# DAC_OutputStage_4.net
KiCad netlist of a schematic drawn in EAGLE
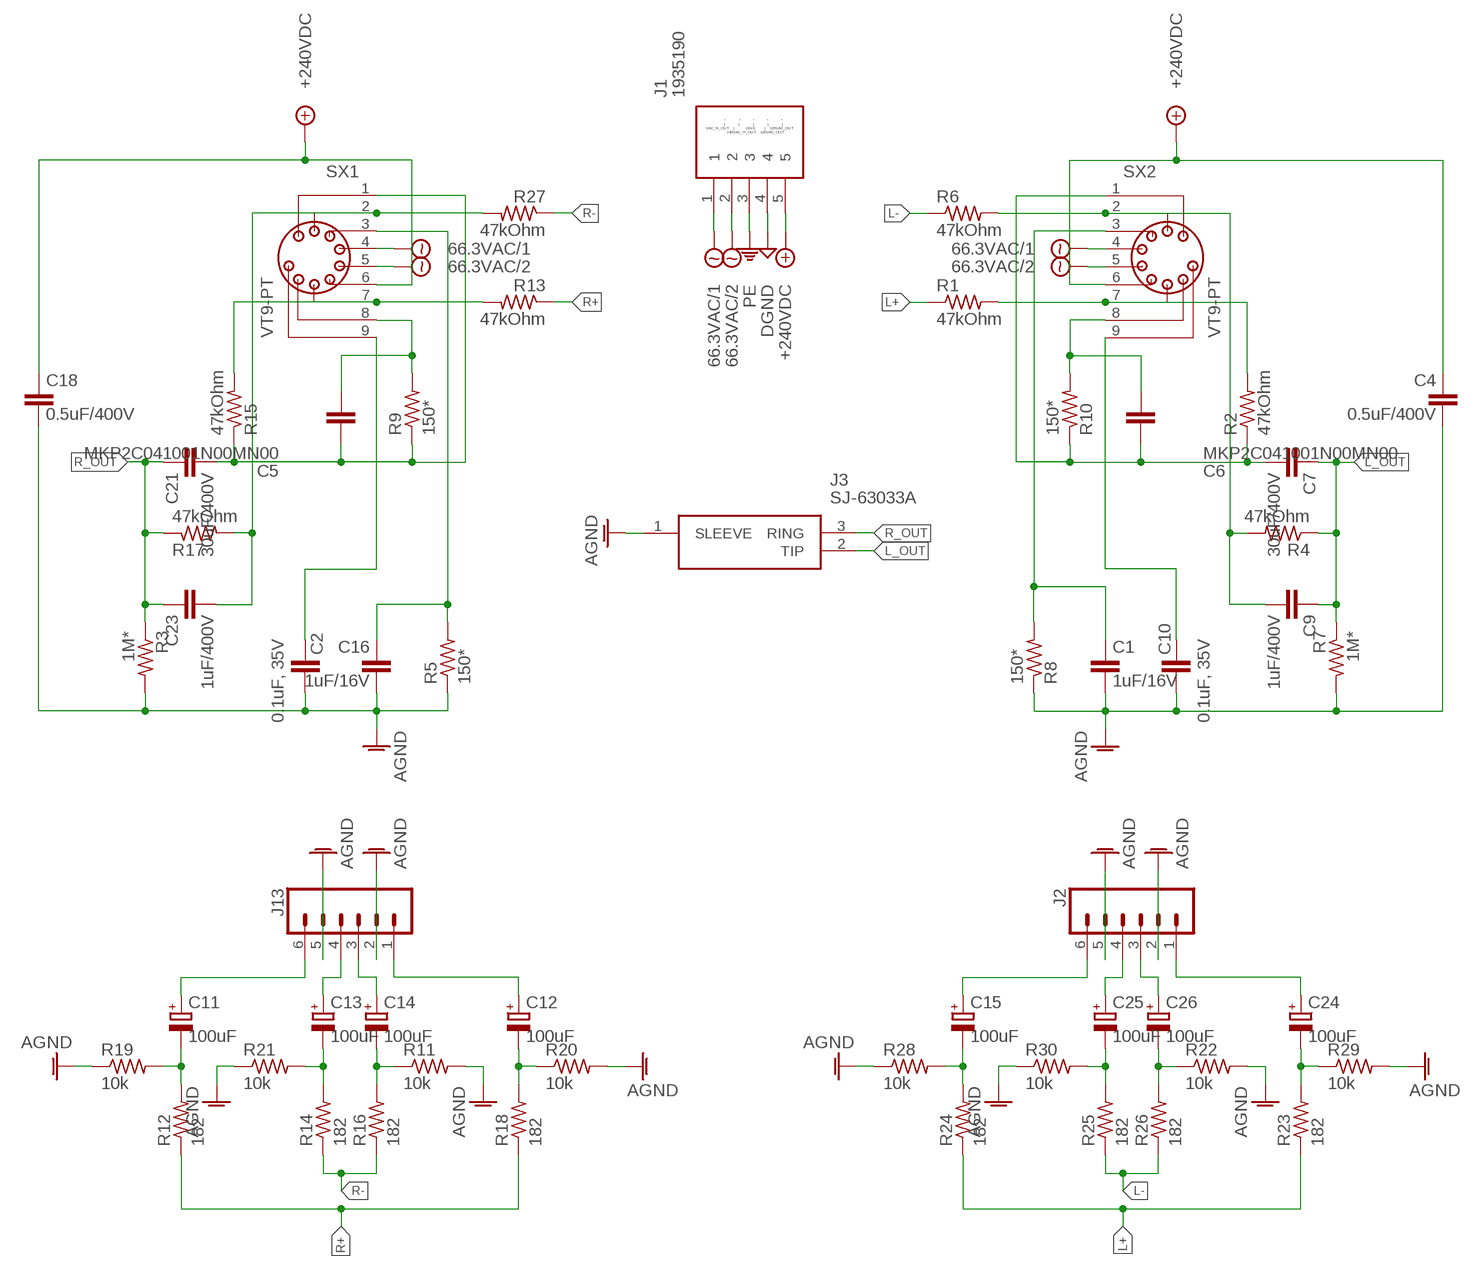
[diagram p0: schematic, sheet 1]

(export (version "E")
  (design (tool "Eeschema 10.0.6"))
  (components
    (comp (ref "C1")
      (value "1uF/16V")
      (footprint "eagle-import:MKP2C041001N00MN00")
      (fields
        (field (name "MANUFACTURER_PART_NUMBER") "MKP2C041001N00MN00")
        (field (name "MOUSER_PART_NUMBER") "505-MKP2C0411NMN")
      )
      (libsource (lib "eagle-import") (part "MKP2C041001N00MN00"))
    )
    (comp (ref "C2")
      (value "0.1uF, 35V")
      (footprint "eagle-import:MKS4B031002A00JC00")
      (fields
        (field (name "MANUFACTURER_PART_NUMBER") "MKS4B031002A00JC00")
        (field (name "MOUSER_PART_NUMBER") "505-MKS4B0312AJC")
      )
      (libsource (lib "eagle-import") (part "MKS4B031002A00JC00"))
    )
    (comp (ref "C4")
      (value "0.5uF/400V")
      (footprint "eagle-import:MKP4G034705D00KSSD")
      (fields
        (field (name "MANUFACTURER_PART_NUMBER") "MKP4G034705D00KSSD")
        (field (name "MOUSER_PART_NUMBER") "505-MKP4G034705DKSSD")
      )
      (libsource (lib "eagle-import") (part "MKP4G034705D00KSSD"))
    )
    (comp (ref "C5")
      (value "MKP2C041001N00MN00")
      (footprint "eagle-import:MKP2C041001N00MN00")
      (fields (field (name "MOUSER_PART_NUMBER") "505-MKP2C0411NMN"))
      (libsource (lib "eagle-import") (part "MKP2C041001N00MN00"))
    )
    (comp (ref "C6")
      (value "MKP2C041001N00MN00")
      (footprint "eagle-import:MKP2C041001N00MN00")
      (fields (field (name "MOUSER_PART_NUMBER") "505-MKP2C0411NMN"))
      (libsource (lib "eagle-import") (part "MKP2C041001N00MN00"))
    )
    (comp (ref "C7")
      (value "30uF/400V")
      (footprint "eagle-import:DCP4G053006ID2KSSD")
      (fields
        (field (name "MANUFACTURER_PART_NUMBER") "DCP4G053006ID2KSSD")
        (field (name "MOUSER_PART_NUMBER") "505-DCP4G0536ID2KSSD")
      )
      (libsource (lib "eagle-import") (part "DCP4G053006ID2KSSD"))
    )
    (comp (ref "C9")
      (value "1uF/400V")
      (footprint "eagle-import:MKP4G041005I00JSSD")
      (fields
        (field (name "MANUFACTURER_PART_NUMBER") "MKP4G041005I00JSSD")
        (field (name "MOUSER_PART_NUMBER") "505-MKP4G041005I00JS")
      )
      (libsource (lib "eagle-import") (part "MKP4G041005I00JSSD"))
    )
    (comp (ref "C10")
      (value "0.1uF, 35V")
      (footprint "eagle-import:MKS4B031002A00JC00")
      (fields
        (field (name "MANUFACTURER_PART_NUMBER") "MKS4B031002A00JC00")
        (field (name "MOUSER_PART_NUMBER") "505-MKS4B0312AJC")
      )
      (libsource (lib "eagle-import") (part "MKS4B031002A00JC00"))
    )
    (comp (ref "C11")
      (value "100uF")
      (footprint "eagle-import:CAPPRD350W60D825H1300")
      (fields
        (field (name "ARROW_PART_NUMBER") "UFW1H101MPD1TD")
        (field (name "MOUSER_PART_NUMBER") "647-UFW1H101MPD1TD")
      )
      (libsource (lib "eagle-import") (part "UFW1H101MPD1TD"))
    )
    (comp (ref "C12")
      (value "100uF")
      (footprint "eagle-import:CAPPRD350W60D825H1300")
      (fields
        (field (name "ARROW_PART_NUMBER") "UFW1H101MPD1TD")
        (field (name "MOUSER_PART_NUMBER") "647-UFW1H101MPD1TD")
      )
      (libsource (lib "eagle-import") (part "UFW1H101MPD1TD"))
    )
    (comp (ref "C13")
      (value "100uF")
      (footprint "eagle-import:CAPPRD350W60D825H1300")
      (fields
        (field (name "ARROW_PART_NUMBER") "UFW1H101MPD1TD")
        (field (name "MOUSER_PART_NUMBER") "647-UFW1H101MPD1TD")
      )
      (libsource (lib "eagle-import") (part "UFW1H101MPD1TD"))
    )
    (comp (ref "C14")
      (value "100uF")
      (footprint "eagle-import:CAPPRD350W60D825H1300")
      (fields
        (field (name "ARROW_PART_NUMBER") "UFW1H101MPD1TD")
        (field (name "MOUSER_PART_NUMBER") "647-UFW1H101MPD1TD")
      )
      (libsource (lib "eagle-import") (part "UFW1H101MPD1TD"))
    )
    (comp (ref "C15")
      (value "100uF")
      (footprint "eagle-import:CAPPRD350W60D825H1300")
      (fields
        (field (name "ARROW_PART_NUMBER") "UFW1H101MPD1TD")
        (field (name "MOUSER_PART_NUMBER") "647-UFW1H101MPD1TD")
      )
      (libsource (lib "eagle-import") (part "UFW1H101MPD1TD"))
    )
    (comp (ref "C16")
      (value "1uF/16V")
      (footprint "eagle-import:MKP2C041001N00MN00")
      (fields
        (field (name "MANUFACTURER_PART_NUMBER") "MKP2C041001N00MN00")
        (field (name "MOUSER_PART_NUMBER") "505-MKP2C0411NMN")
      )
      (libsource (lib "eagle-import") (part "MKP2C041001N00MN00"))
    )
    (comp (ref "C18")
      (value "0.5uF/400V")
      (footprint "eagle-import:MKP4G034705D00KSSD")
      (fields
        (field (name "MANUFACTURER_PART_NUMBER") "MKP4G034705D00KSSD")
        (field (name "MOUSER_PART_NUMBER") "505-MKP4G034705DKSSD")
      )
      (libsource (lib "eagle-import") (part "MKP4G034705D00KSSD"))
    )
    (comp (ref "C21")
      (value "30uF/400V")
      (footprint "eagle-import:DCP4G053006ID2KSSD")
      (fields
        (field (name "MANUFACTURER_PART_NUMBER") "DCP4G053006ID2KSSD")
        (field (name "MOUSER_PART_NUMBER") "505-DCP4G0536ID2KSSD")
      )
      (libsource (lib "eagle-import") (part "DCP4G053006ID2KSSD"))
    )
    (comp (ref "C23")
      (value "1uF/400V")
      (footprint "eagle-import:MKP4G041005I00JSSD")
      (fields
        (field (name "MANUFACTURER_PART_NUMBER") "MKP4G041005I00JSSD")
        (field (name "MOUSER_PART_NUMBER") "505-MKP4G041005I00JS")
      )
      (libsource (lib "eagle-import") (part "MKP4G041005I00JSSD"))
    )
    (comp (ref "C24")
      (value "100uF")
      (footprint "eagle-import:CAPPRD350W60D825H1300")
      (fields
        (field (name "ARROW_PART_NUMBER") "UFW1H101MPD1TD")
        (field (name "MOUSER_PART_NUMBER") "647-UFW1H101MPD1TD")
      )
      (libsource (lib "eagle-import") (part "UFW1H101MPD1TD"))
    )
    (comp (ref "C25")
      (value "100uF")
      (footprint "eagle-import:CAPPRD350W60D825H1300")
      (fields
        (field (name "ARROW_PART_NUMBER") "UFW1H101MPD1TD")
        (field (name "MOUSER_PART_NUMBER") "647-UFW1H101MPD1TD")
      )
      (libsource (lib "eagle-import") (part "UFW1H101MPD1TD"))
    )
    (comp (ref "C26")
      (value "100uF")
      (footprint "eagle-import:CAPPRD350W60D825H1300")
      (fields
        (field (name "ARROW_PART_NUMBER") "UFW1H101MPD1TD")
        (field (name "MOUSER_PART_NUMBER") "647-UFW1H101MPD1TD")
      )
      (libsource (lib "eagle-import") (part "UFW1H101MPD1TD"))
    )
    (comp (ref "J1")
      (value "1935190")
      (footprint "eagle-import:1935190")
      (fields (field (name "MOUSER_PART_NUMBER") "651-1935190"))
      (libsource (lib "eagle-import") (part "1935190"))
    )
    (comp (ref "J2")
      (value "CONN_06SILK_FEMALE_PTH")
      (footprint "eagle-import:1X06")
      (libsource (lib "eagle-import") (part "CONN_06SILK_FEMALE_PTH"))
    )
    (comp (ref "J3")
      (value "SJ-63033A")
      (footprint "eagle-import:SJ63033A")
      (libsource (lib "eagle-import") (part "SJ-63033A"))
    )
    (comp (ref "J13")
      (value "CONN_06SILK_FEMALE_PTH")
      (footprint "eagle-import:1X06")
      (libsource (lib "eagle-import") (part "CONN_06SILK_FEMALE_PTH"))
    )
    (comp (ref "R1")
      (value "47kOhm")
      (footprint "eagle-import:RESAD1540W55L620D230")
      (fields
        (field (name "MANUFACTURER_PART_NUMBER") "LR1F47K")
        (field (name "MOUSER_PART_NUMBER") "279-LR1F47K")
      )
      (libsource (lib "eagle-import") (part "LR1F47K"))
    )
    (comp (ref "R2")
      (value "47kOhm")
      (footprint "eagle-import:RESAD1540W55L620D230")
      (fields
        (field (name "MANUFACTURER_PART_NUMBER") "LR1F47K")
        (field (name "MOUSER_PART_NUMBER") "279-LR1F47K")
      )
      (libsource (lib "eagle-import") (part "LR1F47K"))
    )
    (comp (ref "R3")
      (value "1M*")
      (footprint "eagle-import:RESAD1540W60L620D230")
      (fields
        (field (name "MANUFACTURER_PART_NUMBER") "LR1F1M0")
        (field (name "MOUSER_PART_NUMBER") "279-LR1F1M0")
      )
      (libsource (lib "eagle-import") (part "LR1F1M0"))
    )
    (comp (ref "R4")
      (value "47kOhm")
      (footprint "eagle-import:RESAD1540W55L620D230")
      (fields
        (field (name "MANUFACTURER_PART_NUMBER") "LR1F47K")
        (field (name "MOUSER_PART_NUMBER") "279-LR1F47K")
      )
      (libsource (lib "eagle-import") (part "LR1F47K"))
    )
    (comp (ref "R5")
      (value "150*")
      (footprint "eagle-import:RESAD1540W55L620D230")
      (fields (field (name "MANUFACTURER_PART_NUMBER") "LR1F150R"))
      (libsource (lib "eagle-import") (part "LR1F150R"))
    )
    (comp (ref "R6")
      (value "47kOhm")
      (footprint "eagle-import:RESAD1540W55L620D230")
      (fields
        (field (name "MANUFACTURER_PART_NUMBER") "LR1F47K")
        (field (name "MOUSER_PART_NUMBER") "279-LR1F47K")
      )
      (libsource (lib "eagle-import") (part "LR1F47K"))
    )
    (comp (ref "R7")
      (value "1M*")
      (footprint "eagle-import:RESAD1540W60L620D230")
      (fields
        (field (name "MANUFACTURER_PART_NUMBER") "LR1F1M0")
        (field (name "MOUSER_PART_NUMBER") "279-LR1F1M0")
      )
      (libsource (lib "eagle-import") (part "LR1F1M0"))
    )
    (comp (ref "R8")
      (value "150*")
      (footprint "eagle-import:RESAD1540W55L620D230")
      (fields (field (name "MANUFACTURER_PART_NUMBER") "LR1F150R"))
      (libsource (lib "eagle-import") (part "LR1F150R"))
    )
    (comp (ref "R9")
      (value "150*")
      (footprint "eagle-import:RESAD1540W55L620D230")
      (fields (field (name "MANUFACTURER_PART_NUMBER") "LR1F150R"))
      (libsource (lib "eagle-import") (part "LR1F150R"))
    )
    (comp (ref "R10")
      (value "150*")
      (footprint "eagle-import:RESAD1540W55L620D230")
      (fields (field (name "MANUFACTURER_PART_NUMBER") "LR1F150R"))
      (libsource (lib "eagle-import") (part "LR1F150R"))
    )
    (comp (ref "R11")
      (value "10k")
      (footprint "eagle-import:RESAD1540W55L620D230")
      (fields
        (field (name "MANUFACTURER_PART_NUMBER") "LR1F10K")
        (field (name "MOUSER_PART_NUMBER") "279-LR1F10K")
      )
      (libsource (lib "eagle-import") (part "LR1F10K"))
    )
    (comp (ref "R12")
      (value "182")
      (footprint "eagle-import:RESAD1590W60L630D240")
      (fields (field (name "MANUFACTURER_PART_NUMBER") "MF0207FTE52-182R"))
      (libsource (lib "eagle-import") (part "MF0207FTE52-182R"))
    )
    (comp (ref "R13")
      (value "47kOhm")
      (footprint "eagle-import:RESAD1540W55L620D230")
      (fields
        (field (name "MANUFACTURER_PART_NUMBER") "LR1F47K")
        (field (name "MOUSER_PART_NUMBER") "279-LR1F47K")
      )
      (libsource (lib "eagle-import") (part "LR1F47K"))
    )
    (comp (ref "R14")
      (value "182")
      (footprint "eagle-import:RESAD1590W60L630D240")
      (fields (field (name "MANUFACTURER_PART_NUMBER") "MF0207FTE52-182R"))
      (libsource (lib "eagle-import") (part "MF0207FTE52-182R"))
    )
    (comp (ref "R15")
      (value "47kOhm")
      (footprint "eagle-import:RESAD1540W55L620D230")
      (fields
        (field (name "MANUFACTURER_PART_NUMBER") "LR1F47K")
        (field (name "MOUSER_PART_NUMBER") "279-LR1F47K")
      )
      (libsource (lib "eagle-import") (part "LR1F47K"))
    )
    (comp (ref "R16")
      (value "182")
      (footprint "eagle-import:RESAD1590W60L630D240")
      (fields (field (name "MANUFACTURER_PART_NUMBER") "MF0207FTE52-182R"))
      (libsource (lib "eagle-import") (part "MF0207FTE52-182R"))
    )
    (comp (ref "R17")
      (value "47kOhm")
      (footprint "eagle-import:RESAD1540W55L620D230")
      (fields
        (field (name "MANUFACTURER_PART_NUMBER") "LR1F47K")
        (field (name "MOUSER_PART_NUMBER") "279-LR1F47K")
      )
      (libsource (lib "eagle-import") (part "LR1F47K"))
    )
    (comp (ref "R18")
      (value "182")
      (footprint "eagle-import:RESAD1590W60L630D240")
      (fields (field (name "MANUFACTURER_PART_NUMBER") "MF0207FTE52-182R"))
      (libsource (lib "eagle-import") (part "MF0207FTE52-182R"))
    )
    (comp (ref "R19")
      (value "10k")
      (footprint "eagle-import:RESAD1540W55L620D230")
      (fields
        (field (name "MANUFACTURER_PART_NUMBER") "LR1F10K")
        (field (name "MOUSER_PART_NUMBER") "279-LR1F10K")
      )
      (libsource (lib "eagle-import") (part "LR1F10K"))
    )
    (comp (ref "R20")
      (value "10k")
      (footprint "eagle-import:RESAD1540W55L620D230")
      (fields
        (field (name "MANUFACTURER_PART_NUMBER") "LR1F10K")
        (field (name "MOUSER_PART_NUMBER") "279-LR1F10K")
      )
      (libsource (lib "eagle-import") (part "LR1F10K"))
    )
    (comp (ref "R21")
      (value "10k")
      (footprint "eagle-import:RESAD1540W55L620D230")
      (fields
        (field (name "MANUFACTURER_PART_NUMBER") "LR1F10K")
        (field (name "MOUSER_PART_NUMBER") "279-LR1F10K")
      )
      (libsource (lib "eagle-import") (part "LR1F10K"))
    )
    (comp (ref "R22")
      (value "10k")
      (footprint "eagle-import:RESAD1540W55L620D230")
      (fields
        (field (name "MANUFACTURER_PART_NUMBER") "LR1F10K")
        (field (name "MOUSER_PART_NUMBER") "279-LR1F10K")
      )
      (libsource (lib "eagle-import") (part "LR1F10K"))
    )
    (comp (ref "R23")
      (value "182")
      (footprint "eagle-import:RESAD1590W60L630D240")
      (fields (field (name "MANUFACTURER_PART_NUMBER") "MF0207FTE52-182R"))
      (libsource (lib "eagle-import") (part "MF0207FTE52-182R"))
    )
    (comp (ref "R24")
      (value "182")
      (footprint "eagle-import:RESAD1590W60L630D240")
      (fields (field (name "MANUFACTURER_PART_NUMBER") "MF0207FTE52-182R"))
      (libsource (lib "eagle-import") (part "MF0207FTE52-182R"))
    )
    (comp (ref "R25")
      (value "182")
      (footprint "eagle-import:RESAD1590W60L630D240")
      (fields (field (name "MANUFACTURER_PART_NUMBER") "MF0207FTE52-182R"))
      (libsource (lib "eagle-import") (part "MF0207FTE52-182R"))
    )
    (comp (ref "R26")
      (value "182")
      (footprint "eagle-import:RESAD1590W60L630D240")
      (fields (field (name "MANUFACTURER_PART_NUMBER") "MF0207FTE52-182R"))
      (libsource (lib "eagle-import") (part "MF0207FTE52-182R"))
    )
    (comp (ref "R27")
      (value "47kOhm")
      (footprint "eagle-import:RESAD1540W55L620D230")
      (fields
        (field (name "MANUFACTURER_PART_NUMBER") "LR1F47K")
        (field (name "MOUSER_PART_NUMBER") "279-LR1F47K")
      )
      (libsource (lib "eagle-import") (part "LR1F47K"))
    )
    (comp (ref "R28")
      (value "10k")
      (footprint "eagle-import:RESAD1540W55L620D230")
      (fields
        (field (name "MANUFACTURER_PART_NUMBER") "LR1F10K")
        (field (name "MOUSER_PART_NUMBER") "279-LR1F10K")
      )
      (libsource (lib "eagle-import") (part "LR1F10K"))
    )
    (comp (ref "R29")
      (value "10k")
      (footprint "eagle-import:RESAD1540W55L620D230")
      (fields
        (field (name "MANUFACTURER_PART_NUMBER") "LR1F10K")
        (field (name "MOUSER_PART_NUMBER") "279-LR1F10K")
      )
      (libsource (lib "eagle-import") (part "LR1F10K"))
    )
    (comp (ref "R30")
      (value "10k")
      (footprint "eagle-import:RESAD1540W55L620D230")
      (fields
        (field (name "MANUFACTURER_PART_NUMBER") "LR1F10K")
        (field (name "MOUSER_PART_NUMBER") "279-LR1F10K")
      )
      (libsource (lib "eagle-import") (part "LR1F10K"))
    )
    (comp (ref "SX1")
      (value "VT9-PT")
      (footprint "eagle-import:VT9-PT")
      (libsource (lib "eagle-import") (part "VT9-PT"))
    )
    (comp (ref "SX2")
      (value "VT9-PT")
      (footprint "eagle-import:VT9-PT")
      (libsource (lib "eagle-import") (part "VT9-PT"))
    )
  )
  (nets
    (net (code "1") (name "+240VDC") (class "Default")
      (node (ref "C18") (pin "1") (pinfunction "1_1") (pintype "passive"))
      (node (ref "C4") (pin "1") (pinfunction "1_1") (pintype "passive"))
      (node (ref "J1") (pin "5") (pinfunction "5_5") (pintype "bidirectional"))
      (node (ref "SX1") (pin "6") (pinfunction "6_6") (pintype "passive"))
      (node (ref "SX2") (pin "6") (pinfunction "6_6") (pintype "passive"))
    )
    (net (code "2") (name "66.3VAC{slash}1") (class "Default")
      (node (ref "J1") (pin "1") (pinfunction "1_1") (pintype "bidirectional"))
      (node (ref "SX1") (pin "4") (pinfunction "4_4") (pintype "passive"))
      (node (ref "SX2") (pin "4") (pinfunction "4_4") (pintype "passive"))
    )
    (net (code "3") (name "66.3VAC{slash}2") (class "Default")
      (node (ref "J1") (pin "2") (pinfunction "2_2") (pintype "bidirectional"))
      (node (ref "SX1") (pin "5") (pinfunction "5_5") (pintype "passive"))
      (node (ref "SX2") (pin "5") (pinfunction "5_5") (pintype "passive"))
    )
    (net (code "4") (name "AGND") (class "Default")
      (node (ref "C1") (pin "2") (pinfunction "2_2") (pintype "passive"))
      (node (ref "C10") (pin "2") (pinfunction "2_2") (pintype "passive"))
      (node (ref "C16") (pin "2") (pinfunction "2_2") (pintype "passive"))
      (node (ref "C18") (pin "2") (pinfunction "2_2") (pintype "passive"))
      (node (ref "C2") (pin "2") (pinfunction "2_2") (pintype "passive"))
      (node (ref "C4") (pin "2") (pinfunction "2_2") (pintype "passive"))
      (node (ref "J13") (pin "2") (pinfunction "2_2") (pintype "passive"))
      (node (ref "J13") (pin "5") (pinfunction "5_5") (pintype "passive"))
      (node (ref "J2") (pin "2") (pinfunction "2_2") (pintype "passive"))
      (node (ref "J2") (pin "5") (pinfunction "5_5") (pintype "passive"))
      (node (ref "J3") (pin "1") (pinfunction "SLEEVE_1") (pintype "bidirectional"))
      (node (ref "R11") (pin "2") (pinfunction "2_2") (pintype "passive"))
      (node (ref "R19") (pin "1") (pinfunction "1_1") (pintype "passive"))
      (node (ref "R20") (pin "2") (pinfunction "2_2") (pintype "passive"))
      (node (ref "R21") (pin "1") (pinfunction "1_1") (pintype "passive"))
      (node (ref "R22") (pin "2") (pinfunction "2_2") (pintype "passive"))
      (node (ref "R28") (pin "1") (pinfunction "1_1") (pintype "passive"))
      (node (ref "R29") (pin "2") (pinfunction "2_2") (pintype "passive"))
      (node (ref "R3") (pin "2") (pinfunction "2_2") (pintype "passive"))
      (node (ref "R30") (pin "1") (pinfunction "1_1") (pintype "passive"))
      (node (ref "R5") (pin "1") (pinfunction "1_1") (pintype "passive"))
      (node (ref "R7") (pin "2") (pinfunction "2_2") (pintype "passive"))
      (node (ref "R8") (pin "1") (pinfunction "1_1") (pintype "passive"))
    )
    (net (code "5") (name "DGND") (class "Default")
      (node (ref "J1") (pin "4") (pinfunction "4_4") (pintype "bidirectional"))
    )
    (net (code "6") (name "L+") (class "Default")
      (node (ref "R1") (pin "1") (pinfunction "1_1") (pintype "passive"))
      (node (ref "R23") (pin "1") (pinfunction "1_1") (pintype "passive"))
      (node (ref "R24") (pin "1") (pinfunction "1_1") (pintype "passive"))
    )
    (net (code "7") (name "L-") (class "Default")
      (node (ref "R25") (pin "1") (pinfunction "1_1") (pintype "passive"))
      (node (ref "R26") (pin "1") (pinfunction "1_1") (pintype "passive"))
      (node (ref "R6") (pin "1") (pinfunction "1_1") (pintype "passive"))
    )
    (net (code "8") (name "L_OUT") (class "Default")
      (node (ref "C7") (pin "1") (pinfunction "1_1") (pintype "passive"))
      (node (ref "C9") (pin "1") (pinfunction "1_1") (pintype "passive"))
      (node (ref "J3") (pin "2") (pinfunction "TIP_2") (pintype "bidirectional"))
      (node (ref "R4") (pin "1") (pinfunction "1_1") (pintype "passive"))
      (node (ref "R7") (pin "1") (pinfunction "1_1") (pintype "passive"))
    )
    (net (code "9") (name "Net-(C1-Pad1)") (class "Default")
      (node (ref "C1") (pin "1") (pinfunction "1_1") (pintype "passive"))
      (node (ref "R8") (pin "2") (pinfunction "2_2") (pintype "passive"))
      (node (ref "SX2") (pin "3") (pinfunction "3_3") (pintype "passive"))
    )
    (net (code "10") (name "Net-(C2-Pad1)") (class "Default")
      (node (ref "C2") (pin "1") (pinfunction "1_1") (pintype "passive"))
      (node (ref "SX1") (pin "9") (pinfunction "9_9") (pintype "passive"))
    )
    (net (code "11") (name "Net-(C5-Pad2)") (class "Default")
      (node (ref "C5") (pin "2") (pinfunction "2_2") (pintype "passive"))
      (node (ref "R9") (pin "2") (pinfunction "2_2") (pintype "passive"))
      (node (ref "SX1") (pin "8") (pinfunction "8_8") (pintype "passive"))
    )
    (net (code "12") (name "Net-(C6-Pad1)") (class "Default")
      (node (ref "C6") (pin "1") (pinfunction "1_1") (pintype "passive"))
      (node (ref "C7") (pin "2") (pinfunction "2_2") (pintype "passive"))
      (node (ref "R10") (pin "1") (pinfunction "1_1") (pintype "passive"))
      (node (ref "R2") (pin "1") (pinfunction "1_1") (pintype "passive"))
      (node (ref "SX2") (pin "1") (pinfunction "1_1") (pintype "passive"))
    )
    (net (code "13") (name "Net-(C6-Pad2)") (class "Default")
      (node (ref "C6") (pin "2") (pinfunction "2_2") (pintype "passive"))
      (node (ref "R10") (pin "2") (pinfunction "2_2") (pintype "passive"))
      (node (ref "SX2") (pin "8") (pinfunction "8_8") (pintype "passive"))
    )
    (net (code "14") (name "Net-(C9-Pad2)") (class "Default")
      (node (ref "C9") (pin "2") (pinfunction "2_2") (pintype "passive"))
      (node (ref "R4") (pin "2") (pinfunction "2_2") (pintype "passive"))
      (node (ref "R6") (pin "2") (pinfunction "2_2") (pintype "passive"))
      (node (ref "SX2") (pin "2") (pinfunction "2_2") (pintype "passive"))
    )
    (net (code "15") (name "Net-(C10-Pad1)") (class "Default")
      (node (ref "C10") (pin "1") (pinfunction "1_1") (pintype "passive"))
      (node (ref "SX2") (pin "9") (pinfunction "9_9") (pintype "passive"))
    )
    (net (code "16") (name "Net-(C11-+)") (class "Default")
      (node (ref "C11") (pin "1") (pinfunction "+_1") (pintype "passive"))
      (node (ref "J13") (pin "6") (pinfunction "6_6") (pintype "passive"))
    )
    (net (code "17") (name "Net-(C11--)") (class "Default")
      (node (ref "C11") (pin "2") (pinfunction "-_2") (pintype "passive"))
      (node (ref "R12") (pin "2") (pinfunction "2_2") (pintype "passive"))
      (node (ref "R19") (pin "2") (pinfunction "2_2") (pintype "passive"))
    )
    (net (code "18") (name "Net-(C12-+)") (class "Default")
      (node (ref "C12") (pin "1") (pinfunction "+_1") (pintype "passive"))
      (node (ref "J13") (pin "1") (pinfunction "1_1") (pintype "passive"))
    )
    (net (code "19") (name "Net-(C12--)") (class "Default")
      (node (ref "C12") (pin "2") (pinfunction "-_2") (pintype "passive"))
      (node (ref "R18") (pin "2") (pinfunction "2_2") (pintype "passive"))
      (node (ref "R20") (pin "1") (pinfunction "1_1") (pintype "passive"))
    )
    (net (code "20") (name "Net-(C13-+)") (class "Default")
      (node (ref "C13") (pin "1") (pinfunction "+_1") (pintype "passive"))
      (node (ref "J13") (pin "4") (pinfunction "4_4") (pintype "passive"))
    )
    (net (code "21") (name "Net-(C13--)") (class "Default")
      (node (ref "C13") (pin "2") (pinfunction "-_2") (pintype "passive"))
      (node (ref "R14") (pin "2") (pinfunction "2_2") (pintype "passive"))
      (node (ref "R21") (pin "2") (pinfunction "2_2") (pintype "passive"))
    )
    (net (code "22") (name "Net-(C14-+)") (class "Default")
      (node (ref "C14") (pin "1") (pinfunction "+_1") (pintype "passive"))
      (node (ref "J13") (pin "3") (pinfunction "3_3") (pintype "passive"))
    )
    (net (code "23") (name "Net-(C14--)") (class "Default")
      (node (ref "C14") (pin "2") (pinfunction "-_2") (pintype "passive"))
      (node (ref "R11") (pin "1") (pinfunction "1_1") (pintype "passive"))
      (node (ref "R16") (pin "2") (pinfunction "2_2") (pintype "passive"))
    )
    (net (code "24") (name "Net-(C15-+)") (class "Default")
      (node (ref "C15") (pin "1") (pinfunction "+_1") (pintype "passive"))
      (node (ref "J2") (pin "6") (pinfunction "6_6") (pintype "passive"))
    )
    (net (code "25") (name "Net-(C15--)") (class "Default")
      (node (ref "C15") (pin "2") (pinfunction "-_2") (pintype "passive"))
      (node (ref "R24") (pin "2") (pinfunction "2_2") (pintype "passive"))
      (node (ref "R28") (pin "2") (pinfunction "2_2") (pintype "passive"))
    )
    (net (code "26") (name "Net-(C16-Pad1)") (class "Default")
      (node (ref "C16") (pin "1") (pinfunction "1_1") (pintype "passive"))
      (node (ref "R5") (pin "2") (pinfunction "2_2") (pintype "passive"))
      (node (ref "SX1") (pin "3") (pinfunction "3_3") (pintype "passive"))
    )
    (net (code "27") (name "Net-(C21-Pad2)") (class "Default")
      (node (ref "C21") (pin "2") (pinfunction "2_2") (pintype "passive"))
      (node (ref "C5") (pin "1") (pinfunction "1_1") (pintype "passive"))
      (node (ref "R15") (pin "1") (pinfunction "1_1") (pintype "passive"))
      (node (ref "R9") (pin "1") (pinfunction "1_1") (pintype "passive"))
      (node (ref "SX1") (pin "1") (pinfunction "1_1") (pintype "passive"))
    )
    (net (code "28") (name "Net-(C23-Pad2)") (class "Default")
      (node (ref "C23") (pin "2") (pinfunction "2_2") (pintype "passive"))
      (node (ref "R17") (pin "2") (pinfunction "2_2") (pintype "passive"))
      (node (ref "R27") (pin "2") (pinfunction "2_2") (pintype "passive"))
      (node (ref "SX1") (pin "2") (pinfunction "2_2") (pintype "passive"))
    )
    (net (code "29") (name "Net-(C24-+)") (class "Default")
      (node (ref "C24") (pin "1") (pinfunction "+_1") (pintype "passive"))
      (node (ref "J2") (pin "1") (pinfunction "1_1") (pintype "passive"))
    )
    (net (code "30") (name "Net-(C24--)") (class "Default")
      (node (ref "C24") (pin "2") (pinfunction "-_2") (pintype "passive"))
      (node (ref "R23") (pin "2") (pinfunction "2_2") (pintype "passive"))
      (node (ref "R29") (pin "1") (pinfunction "1_1") (pintype "passive"))
    )
    (net (code "31") (name "Net-(C25-+)") (class "Default")
      (node (ref "C25") (pin "1") (pinfunction "+_1") (pintype "passive"))
      (node (ref "J2") (pin "4") (pinfunction "4_4") (pintype "passive"))
    )
    (net (code "32") (name "Net-(C25--)") (class "Default")
      (node (ref "C25") (pin "2") (pinfunction "-_2") (pintype "passive"))
      (node (ref "R25") (pin "2") (pinfunction "2_2") (pintype "passive"))
      (node (ref "R30") (pin "2") (pinfunction "2_2") (pintype "passive"))
    )
    (net (code "33") (name "Net-(C26-+)") (class "Default")
      (node (ref "C26") (pin "1") (pinfunction "+_1") (pintype "passive"))
      (node (ref "J2") (pin "3") (pinfunction "3_3") (pintype "passive"))
    )
    (net (code "34") (name "Net-(C26--)") (class "Default")
      (node (ref "C26") (pin "2") (pinfunction "-_2") (pintype "passive"))
      (node (ref "R22") (pin "1") (pinfunction "1_1") (pintype "passive"))
      (node (ref "R26") (pin "2") (pinfunction "2_2") (pintype "passive"))
    )
    (net (code "35") (name "Net-(R1-Pad2)") (class "Default")
      (node (ref "R1") (pin "2") (pinfunction "2_2") (pintype "passive"))
      (node (ref "R2") (pin "2") (pinfunction "2_2") (pintype "passive"))
      (node (ref "SX2") (pin "7") (pinfunction "7_7") (pintype "passive"))
    )
    (net (code "36") (name "Net-(R13-Pad2)") (class "Default")
      (node (ref "R13") (pin "2") (pinfunction "2_2") (pintype "passive"))
      (node (ref "R15") (pin "2") (pinfunction "2_2") (pintype "passive"))
      (node (ref "SX1") (pin "7") (pinfunction "7_7") (pintype "passive"))
    )
    (net (code "37") (name "PE") (class "Default")
      (node (ref "J1") (pin "3") (pinfunction "3_3") (pintype "bidirectional"))
    )
    (net (code "38") (name "R+") (class "Default")
      (node (ref "R12") (pin "1") (pinfunction "1_1") (pintype "passive"))
      (node (ref "R13") (pin "1") (pinfunction "1_1") (pintype "passive"))
      (node (ref "R18") (pin "1") (pinfunction "1_1") (pintype "passive"))
    )
    (net (code "39") (name "R-") (class "Default")
      (node (ref "R14") (pin "1") (pinfunction "1_1") (pintype "passive"))
      (node (ref "R16") (pin "1") (pinfunction "1_1") (pintype "passive"))
      (node (ref "R27") (pin "1") (pinfunction "1_1") (pintype "passive"))
    )
    (net (code "40") (name "R_OUT") (class "Default")
      (node (ref "C21") (pin "1") (pinfunction "1_1") (pintype "passive"))
      (node (ref "C23") (pin "1") (pinfunction "1_1") (pintype "passive"))
      (node (ref "J3") (pin "3") (pinfunction "RING_3") (pintype "bidirectional"))
      (node (ref "R17") (pin "1") (pinfunction "1_1") (pintype "passive"))
      (node (ref "R3") (pin "1") (pinfunction "1_1") (pintype "passive"))
    )
  )
)
